# OBCI32_HC05.net
KiCad netlist of a schematic drawn in EAGLE
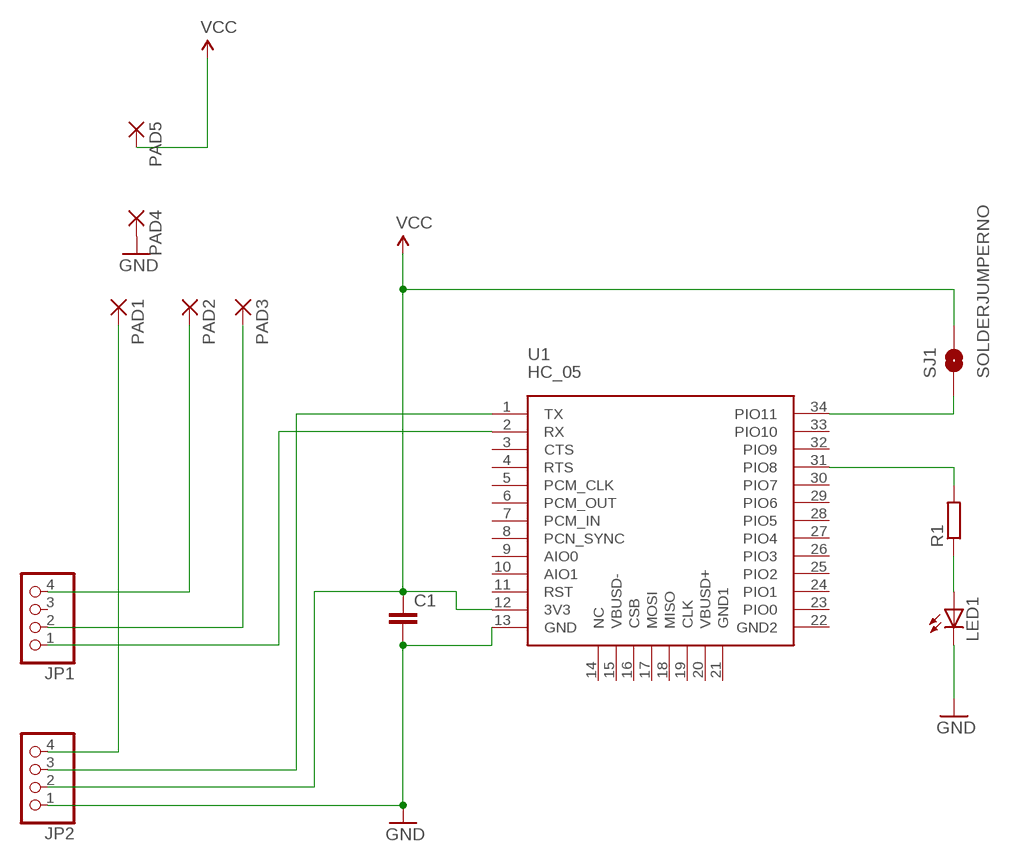
[diagram p0: schematic, sheet 1]

(export (version "E")
  (design (tool "Eeschema 10.0.6"))
  (components
    (comp (ref "C1")
      (value "C-EUC0805")
      (footprint "eagle-import:C0805")
      (libsource (lib "eagle-import") (part "C-EUC0805"))
    )
    (comp (ref "JP1")
      (value "PINHD-1X4")
      (footprint "eagle-import:1X04")
      (libsource (lib "eagle-import") (part "PINHD-1X4"))
    )
    (comp (ref "JP2")
      (value "PINHD-1X4")
      (footprint "eagle-import:1X04")
      (libsource (lib "eagle-import") (part "PINHD-1X4"))
    )
    (comp (ref "LED1")
      (value "LEDCHIP-LED0805")
      (footprint "eagle-import:CHIP-LED0805")
      (libsource (lib "eagle-import") (part "LEDCHIP-LED0805"))
    )
    (comp (ref "PAD1")
      (value "SMD2")
      (footprint "eagle-import:SMD1,27-2,54")
      (libsource (lib "eagle-import") (part "SMD2"))
    )
    (comp (ref "PAD2")
      (value "SMD2")
      (footprint "eagle-import:SMD1,27-2,54")
      (libsource (lib "eagle-import") (part "SMD2"))
    )
    (comp (ref "PAD3")
      (value "SMD2")
      (footprint "eagle-import:SMD1,27-2,54")
      (libsource (lib "eagle-import") (part "SMD2"))
    )
    (comp (ref "PAD4")
      (value "SMD2")
      (footprint "eagle-import:SMD1,27-2,54")
      (libsource (lib "eagle-import") (part "SMD2"))
    )
    (comp (ref "PAD5")
      (value "SMD2")
      (footprint "eagle-import:SMD1,27-2,54")
      (libsource (lib "eagle-import") (part "SMD2"))
    )
    (comp (ref "R1")
      (value "R-EU_R0603")
      (footprint "eagle-import:R0603")
      (libsource (lib "eagle-import") (part "R-EU_R0603"))
    )
    (comp (ref "SJ1")
      (value "SOLDERJUMPERNO")
      (footprint "eagle-import:SJ_2S-NO")
      (libsource (lib "eagle-import") (part "SOLDERJUMPERNO"))
    )
    (comp (ref "U1")
      (value "HC_05")
      (footprint "eagle-import:BLUETOOTH_SMD")
      (libsource (lib "eagle-import") (part "HC_05"))
    )
  )
  (nets
    (net (code "1") (name "GND") (class "Default")
      (node (ref "C1") (pin "2") (pinfunction "2_2") (pintype "passive"))
      (node (ref "JP2") (pin "1") (pinfunction "1_1") (pintype "passive"))
      (node (ref "LED1") (pin "C") (pinfunction "C_C") (pintype "passive"))
      (node (ref "PAD4") (pin "1") (pinfunction "P_1") (pintype "passive"))
      (node (ref "U1") (pin "13") (pinfunction "GND_13") (pintype "bidirectional"))
    )
    (net (code "2") (name "Net-(LED1-PadA)") (class "Default")
      (node (ref "LED1") (pin "A") (pinfunction "A_A") (pintype "passive"))
      (node (ref "R1") (pin "1") (pinfunction "1_1") (pintype "passive"))
    )
    (net (code "3") (name "Net-(PAD1-P)") (class "Default")
      (node (ref "JP2") (pin "4") (pinfunction "4_4") (pintype "passive"))
      (node (ref "PAD1") (pin "1") (pinfunction "P_1") (pintype "passive"))
    )
    (net (code "4") (name "Net-(PAD2-P)") (class "Default")
      (node (ref "JP1") (pin "4") (pinfunction "4_4") (pintype "passive"))
      (node (ref "PAD2") (pin "1") (pinfunction "P_1") (pintype "passive"))
    )
    (net (code "5") (name "Net-(PAD3-P)") (class "Default")
      (node (ref "JP1") (pin "2") (pinfunction "2_2") (pintype "passive"))
      (node (ref "PAD3") (pin "1") (pinfunction "P_1") (pintype "passive"))
    )
    (net (code "6") (name "Net-(U1-PIO8)") (class "Default")
      (node (ref "R1") (pin "2") (pinfunction "2_2") (pintype "passive"))
      (node (ref "U1") (pin "31") (pinfunction "PIO8_31") (pintype "bidirectional"))
    )
    (net (code "7") (name "Net-(U1-PIO11)") (class "Default")
      (node (ref "SJ1") (pin "1") (pinfunction "1_1") (pintype "passive"))
      (node (ref "U1") (pin "34") (pinfunction "PIO11_34") (pintype "bidirectional"))
    )
    (net (code "8") (name "Net-(U1-RX)") (class "Default")
      (node (ref "JP1") (pin "1") (pinfunction "1_1") (pintype "passive"))
      (node (ref "U1") (pin "2") (pinfunction "RX_2") (pintype "bidirectional"))
    )
    (net (code "9") (name "Net-(U1-TX)") (class "Default")
      (node (ref "JP2") (pin "3") (pinfunction "3_3") (pintype "passive"))
      (node (ref "U1") (pin "1") (pinfunction "TX_1") (pintype "bidirectional"))
    )
    (net (code "10") (name "VCC") (class "Default")
      (node (ref "C1") (pin "1") (pinfunction "1_1") (pintype "passive"))
      (node (ref "JP2") (pin "2") (pinfunction "2_2") (pintype "passive"))
      (node (ref "PAD5") (pin "1") (pinfunction "P_1") (pintype "passive"))
      (node (ref "SJ1") (pin "2") (pinfunction "2_2") (pintype "passive"))
      (node (ref "U1") (pin "12") (pinfunction "3V3_12") (pintype "bidirectional"))
    )
    (net (code "11") (name "unconnected-(JP1-Pad3)") (class "Default")
      (node (ref "JP1") (pin "3") (pinfunction "3_3") (pintype "passive"))
    )
    (net (code "12") (name "unconnected-(U1-AIO0-Pad9)") (class "Default")
      (node (ref "U1") (pin "9") (pinfunction "AIO0_9") (pintype "bidirectional"))
    )
    (net (code "13") (name "unconnected-(U1-AIO1-Pad10)") (class "Default")
      (node (ref "U1") (pin "10") (pinfunction "AIO1_10") (pintype "bidirectional"))
    )
    (net (code "14") (name "unconnected-(U1-CLK-Pad19)") (class "Default")
      (node (ref "U1") (pin "19") (pinfunction "CLK_19") (pintype "bidirectional"))
    )
    (net (code "15") (name "unconnected-(U1-CSB-Pad16)") (class "Default")
      (node (ref "U1") (pin "16") (pinfunction "CSB_16") (pintype "bidirectional"))
    )
    (net (code "16") (name "unconnected-(U1-CTS-Pad3)") (class "Default")
      (node (ref "U1") (pin "3") (pinfunction "CTS_3") (pintype "bidirectional"))
    )
    (net (code "17") (name "unconnected-(U1-GND1-Pad21)") (class "Default")
      (node (ref "U1") (pin "21") (pinfunction "GND1_21") (pintype "bidirectional"))
    )
    (net (code "18") (name "unconnected-(U1-GND2-Pad22)") (class "Default")
      (node (ref "U1") (pin "22") (pinfunction "GND2_22") (pintype "bidirectional"))
    )
    (net (code "19") (name "unconnected-(U1-MISO-Pad18)") (class "Default")
      (node (ref "U1") (pin "18") (pinfunction "MISO_18") (pintype "bidirectional"))
    )
    (net (code "20") (name "unconnected-(U1-MOSI-Pad17)") (class "Default")
      (node (ref "U1") (pin "17") (pinfunction "MOSI_17") (pintype "bidirectional"))
    )
    (net (code "21") (name "unconnected-(U1-NC-Pad14)") (class "Default")
      (node (ref "U1") (pin "14") (pinfunction "NC_14") (pintype "bidirectional"))
    )
    (net (code "22") (name "unconnected-(U1-PCM_CLK-Pad5)") (class "Default")
      (node (ref "U1") (pin "5") (pinfunction "PCM_CLK_5") (pintype "bidirectional"))
    )
    (net (code "23") (name "unconnected-(U1-PCM_IN-Pad7)") (class "Default")
      (node (ref "U1") (pin "7") (pinfunction "PCM_IN_7") (pintype "bidirectional"))
    )
    (net (code "24") (name "unconnected-(U1-PCM_OUT-Pad6)") (class "Default")
      (node (ref "U1") (pin "6") (pinfunction "PCM_OUT_6") (pintype "bidirectional"))
    )
    (net (code "25") (name "unconnected-(U1-PCN_SYNC-Pad8)") (class "Default")
      (node (ref "U1") (pin "8") (pinfunction "PCN_SYNC_8") (pintype "bidirectional"))
    )
    (net (code "26") (name "unconnected-(U1-PIO0-Pad23)") (class "Default")
      (node (ref "U1") (pin "23") (pinfunction "PIO0_23") (pintype "bidirectional"))
    )
    (net (code "27") (name "unconnected-(U1-PIO1-Pad24)") (class "Default")
      (node (ref "U1") (pin "24") (pinfunction "PIO1_24") (pintype "bidirectional"))
    )
    (net (code "28") (name "unconnected-(U1-PIO2-Pad25)") (class "Default")
      (node (ref "U1") (pin "25") (pinfunction "PIO2_25") (pintype "bidirectional"))
    )
    (net (code "29") (name "unconnected-(U1-PIO3-Pad26)") (class "Default")
      (node (ref "U1") (pin "26") (pinfunction "PIO3_26") (pintype "bidirectional"))
    )
    (net (code "30") (name "unconnected-(U1-PIO4-Pad27)") (class "Default")
      (node (ref "U1") (pin "27") (pinfunction "PIO4_27") (pintype "bidirectional"))
    )
    (net (code "31") (name "unconnected-(U1-PIO5-Pad28)") (class "Default")
      (node (ref "U1") (pin "28") (pinfunction "PIO5_28") (pintype "bidirectional"))
    )
    (net (code "32") (name "unconnected-(U1-PIO6-Pad29)") (class "Default")
      (node (ref "U1") (pin "29") (pinfunction "PIO6_29") (pintype "bidirectional"))
    )
    (net (code "33") (name "unconnected-(U1-PIO7-Pad30)") (class "Default")
      (node (ref "U1") (pin "30") (pinfunction "PIO7_30") (pintype "bidirectional"))
    )
    (net (code "34") (name "unconnected-(U1-PIO9-Pad32)") (class "Default")
      (node (ref "U1") (pin "32") (pinfunction "PIO9_32") (pintype "bidirectional"))
    )
    (net (code "35") (name "unconnected-(U1-PIO10-Pad33)") (class "Default")
      (node (ref "U1") (pin "33") (pinfunction "PIO10_33") (pintype "bidirectional"))
    )
    (net (code "36") (name "unconnected-(U1-RST-Pad11)") (class "Default")
      (node (ref "U1") (pin "11") (pinfunction "RST_11") (pintype "bidirectional"))
    )
    (net (code "37") (name "unconnected-(U1-RTS-Pad4)") (class "Default")
      (node (ref "U1") (pin "4") (pinfunction "RTS_4") (pintype "bidirectional"))
    )
    (net (code "38") (name "unconnected-(U1-VBUSD+-Pad20)") (class "Default")
      (node (ref "U1") (pin "20") (pinfunction "VBUSD+_20") (pintype "bidirectional"))
    )
    (net (code "39") (name "unconnected-(U1-VBUSD--Pad15)") (class "Default")
      (node (ref "U1") (pin "15") (pinfunction "VBUSD-_15") (pintype "bidirectional"))
    )
  )
)
